# LB_BIT_CLOUD-v03_1_1x.net
KiCad netlist of a schematic drawn in EAGLE
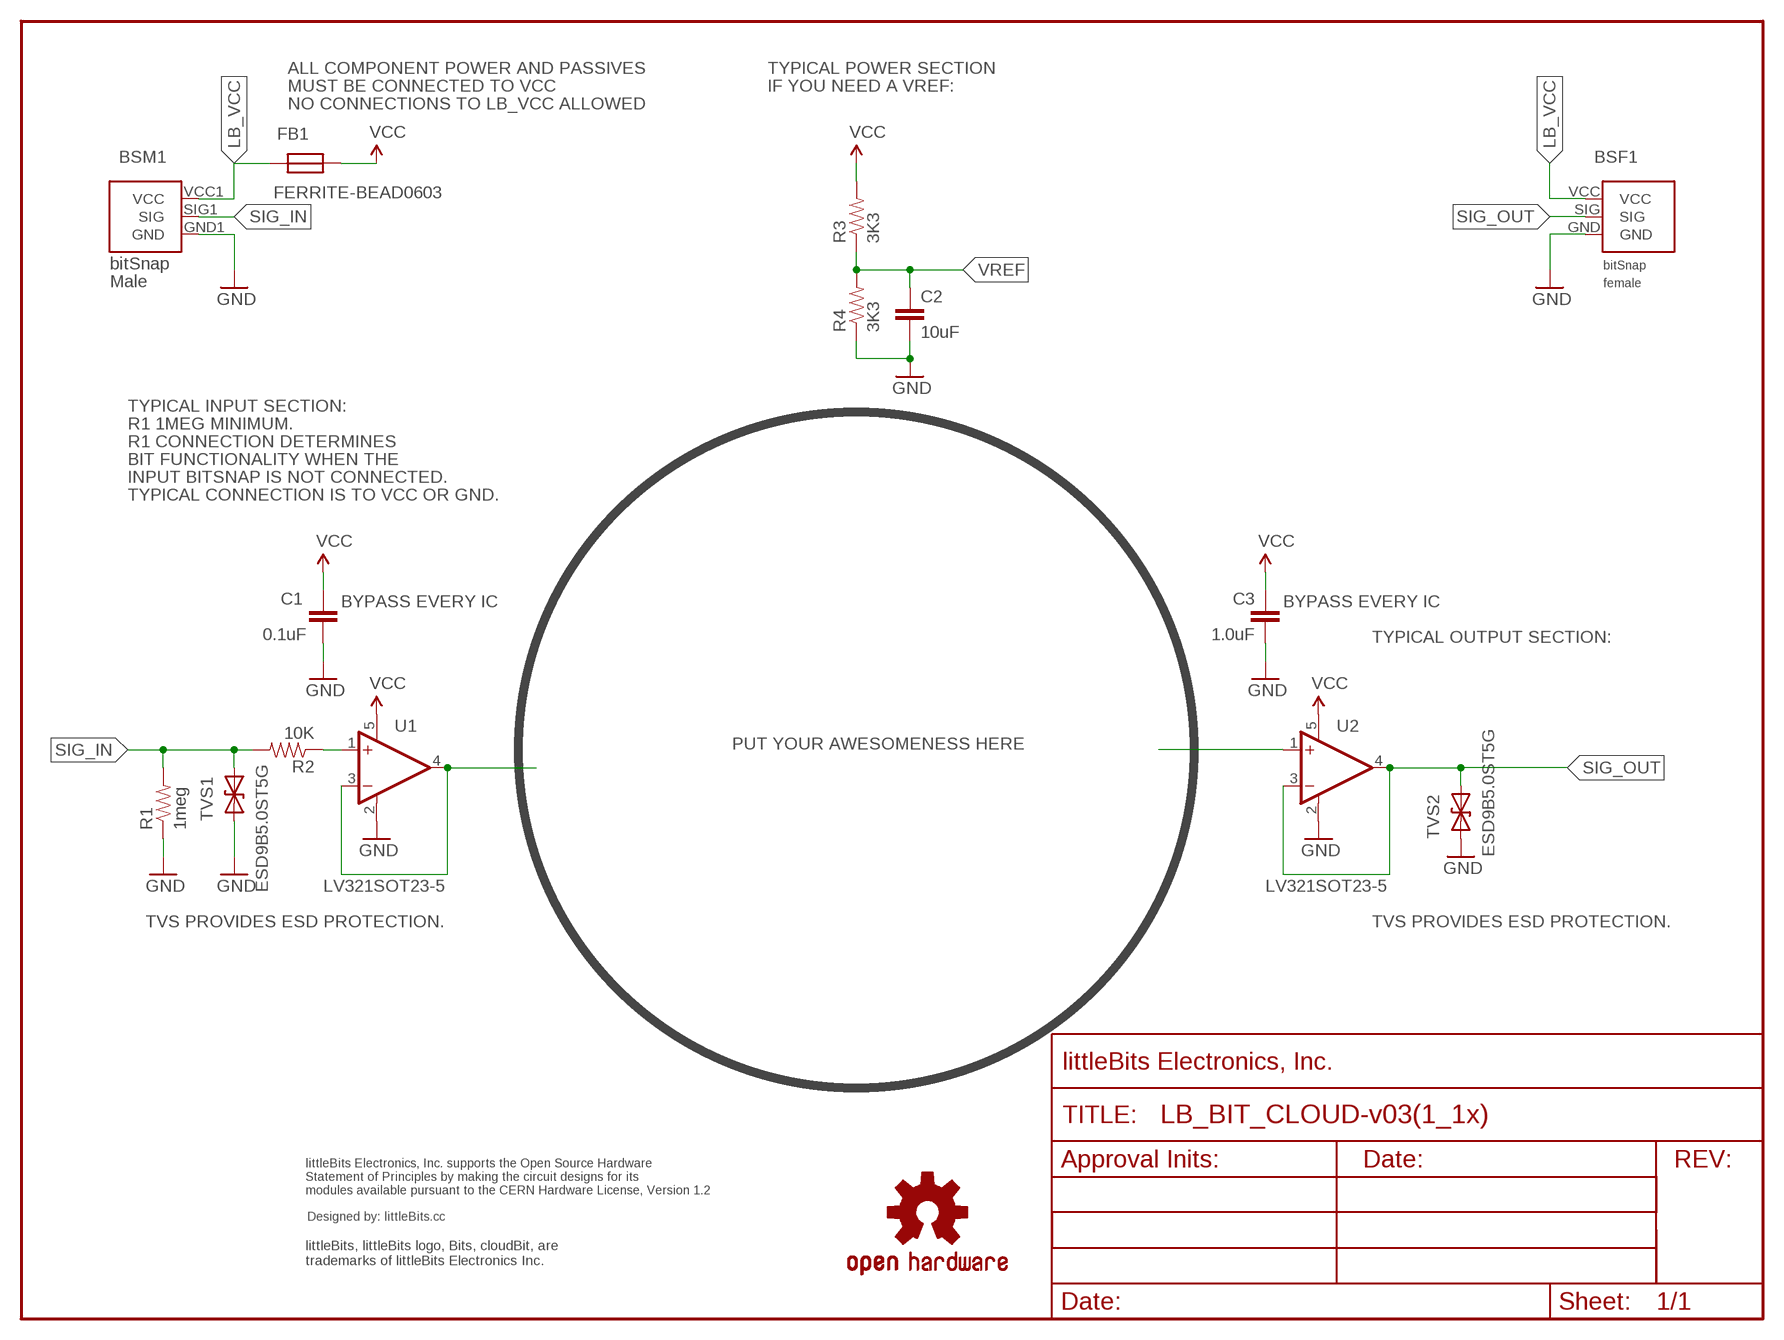
[diagram p0: schematic, sheet 1]

(export (version "E")
  (design (tool "Eeschema 10.0.6"))
  (components
    (comp (ref "BSF1")
      (value "BITSNAP_V03_FEMALE")
      (footprint "eagle-import:BITSNAP_V03_FEMALE")
      (libsource (lib "eagle-import") (part "BITSNAP_V03_FEMALE"))
    )
    (comp (ref "BSM1")
      (value "BITSNAP_V03_MALE")
      (footprint "eagle-import:BITSNAP_V03_MALE")
      (libsource (lib "eagle-import") (part "BITSNAP_V03_MALE"))
    )
    (comp (ref "C1")
      (value "0.1uF")
      (footprint "eagle-import:CAP-0603")
      (libsource (lib "eagle-import") (part "CAPCAP-0603"))
    )
    (comp (ref "C2")
      (value "10uF")
      (footprint "eagle-import:CAP-0603")
      (libsource (lib "eagle-import") (part "CAPCAP-0603"))
    )
    (comp (ref "C3")
      (value "1.0uF")
      (footprint "eagle-import:CAP-0603")
      (libsource (lib "eagle-import") (part "CAPCAP-0603"))
    )
    (comp (ref "FB1")
      (value "FERRITE-BEAD0603")
      (footprint "eagle-import:R0603")
      (libsource (lib "eagle-import") (part "FERRITE-BEAD0603"))
    )
    (comp (ref "FRAME1")
      (value "FRAME-LETTER")
      (footprint "eagle-import:FABDWG01-OHW")
      (libsource (lib "eagle-import") (part "FRAME-LETTER"))
    )
    (comp (ref "R1")
      (value "1meg")
      (footprint "eagle-import:RES-0603")
      (libsource (lib "eagle-import") (part "RESISTOR0603"))
    )
    (comp (ref "R2")
      (value "10K")
      (footprint "eagle-import:RES-0603")
      (libsource (lib "eagle-import") (part "RESISTOR0603"))
    )
    (comp (ref "R3")
      (value "3K3")
      (footprint "eagle-import:RES-0603")
      (libsource (lib "eagle-import") (part "RESISTOR0603"))
    )
    (comp (ref "R4")
      (value "3K3")
      (footprint "eagle-import:RES-0603")
      (libsource (lib "eagle-import") (part "RESISTOR0603"))
    )
    (comp (ref "TVS1")
      (value "ESD9B5.0ST5G")
      (footprint "eagle-import:SOD-923")
      (libsource (lib "eagle-import") (part "DIODE-TVSSOD-923"))
    )
    (comp (ref "TVS2")
      (value "ESD9B5.0ST5G")
      (footprint "eagle-import:SOD-923")
      (libsource (lib "eagle-import") (part "DIODE-TVSSOD-923"))
    )
    (comp (ref "U$3")
      (value "OSHWCREDIT")
      (footprint "eagle-import:OSHWCREDIT")
      (libsource (lib "eagle-import") (part "OSHWCREDIT"))
    )
    (comp (ref "U$4")
      (value "OSHW-LOGOL")
      (footprint "eagle-import:OSHW-LOGO-L")
      (libsource (lib "eagle-import") (part "OSHW-LOGOL"))
    )
    (comp (ref "U1")
      (value "LV321SOT23-5")
      (footprint "eagle-import:SOT23-5")
      (libsource (lib "eagle-import") (part "LV321SOT23-5"))
    )
    (comp (ref "U2")
      (value "LV321SOT23-5")
      (footprint "eagle-import:SOT23-5")
      (libsource (lib "eagle-import") (part "LV321SOT23-5"))
    )
  )
  (nets
    (net (code "1") (name "GND") (class "Default")
      (node (ref "BSF1") (pin "GND") (pinfunction "GND_GND") (pintype "bidirectional"))
      (node (ref "BSM1") (pin "GND1") (pinfunction "GND_GND1") (pintype "bidirectional"))
      (node (ref "C1") (pin "2") (pinfunction "2_2") (pintype "passive"))
      (node (ref "C2") (pin "2") (pinfunction "2_2") (pintype "passive"))
      (node (ref "C3") (pin "1") (pinfunction "1_1") (pintype "passive"))
      (node (ref "R1") (pin "1") (pinfunction "1_1") (pintype "passive"))
      (node (ref "R4") (pin "1") (pinfunction "1_1") (pintype "passive"))
      (node (ref "TVS1") (pin "1") (pinfunction "A_1") (pintype "passive"))
      (node (ref "TVS2") (pin "1") (pinfunction "A_1") (pintype "passive"))
      (node (ref "U1") (pin "2") (pinfunction "V-_2") (pintype "power_in"))
      (node (ref "U2") (pin "2") (pinfunction "V-_2") (pintype "power_in"))
    )
    (net (code "2") (name "LB_VCC") (class "Default")
      (node (ref "BSF1") (pin "VCC") (pinfunction "VCC_VCC") (pintype "bidirectional"))
      (node (ref "BSM1") (pin "VCC1") (pinfunction "VCC_VCC1") (pintype "bidirectional"))
      (node (ref "FB1") (pin "2") (pinfunction "P$2_2") (pintype "bidirectional"))
    )
    (net (code "3") (name "Net-(U1-+IN)") (class "Default")
      (node (ref "R2") (pin "1") (pinfunction "1_1") (pintype "passive"))
      (node (ref "U1") (pin "1") (pinfunction "+IN_1") (pintype "input"))
    )
    (net (code "4") (name "Net-(U1--IN)") (class "Default")
      (node (ref "U1") (pin "3") (pinfunction "-IN_3") (pintype "input"))
      (node (ref "U1") (pin "4") (pinfunction "OUT_4") (pintype "output"))
    )
    (net (code "5") (name "SIG_IN") (class "Default")
      (node (ref "BSM1") (pin "SIG1") (pinfunction "SIG_SIG1") (pintype "bidirectional"))
      (node (ref "R1") (pin "2") (pinfunction "2_2") (pintype "passive"))
      (node (ref "R2") (pin "2") (pinfunction "2_2") (pintype "passive"))
      (node (ref "TVS1") (pin "2") (pinfunction "C_2") (pintype "passive"))
    )
    (net (code "6") (name "SIG_OUT") (class "Default")
      (node (ref "BSF1") (pin "SIG") (pinfunction "SIG_SIG") (pintype "bidirectional"))
      (node (ref "TVS2") (pin "2") (pinfunction "C_2") (pintype "passive"))
      (node (ref "U2") (pin "3") (pinfunction "-IN_3") (pintype "input"))
      (node (ref "U2") (pin "4") (pinfunction "OUT_4") (pintype "output"))
    )
    (net (code "7") (name "VCC") (class "Default")
      (node (ref "C1") (pin "1") (pinfunction "1_1") (pintype "passive"))
      (node (ref "C3") (pin "2") (pinfunction "2_2") (pintype "passive"))
      (node (ref "FB1") (pin "1") (pinfunction "P$1_1") (pintype "bidirectional"))
      (node (ref "R3") (pin "2") (pinfunction "2_2") (pintype "passive"))
      (node (ref "U1") (pin "5") (pinfunction "V+_5") (pintype "power_in"))
      (node (ref "U2") (pin "5") (pinfunction "V+_5") (pintype "power_in"))
    )
    (net (code "8") (name "VREF") (class "Default")
      (node (ref "C2") (pin "1") (pinfunction "1_1") (pintype "passive"))
      (node (ref "R3") (pin "1") (pinfunction "1_1") (pintype "passive"))
      (node (ref "R4") (pin "2") (pinfunction "2_2") (pintype "passive"))
    )
    (net (code "9") (name "unconnected-(U2-+IN-Pad1)") (class "Default")
      (node (ref "U2") (pin "1") (pinfunction "+IN_1") (pintype "input"))
    )
  )
)
